# Schematic_Band_Pass.net
KiCad netlist of a schematic drawn in Altium Designer
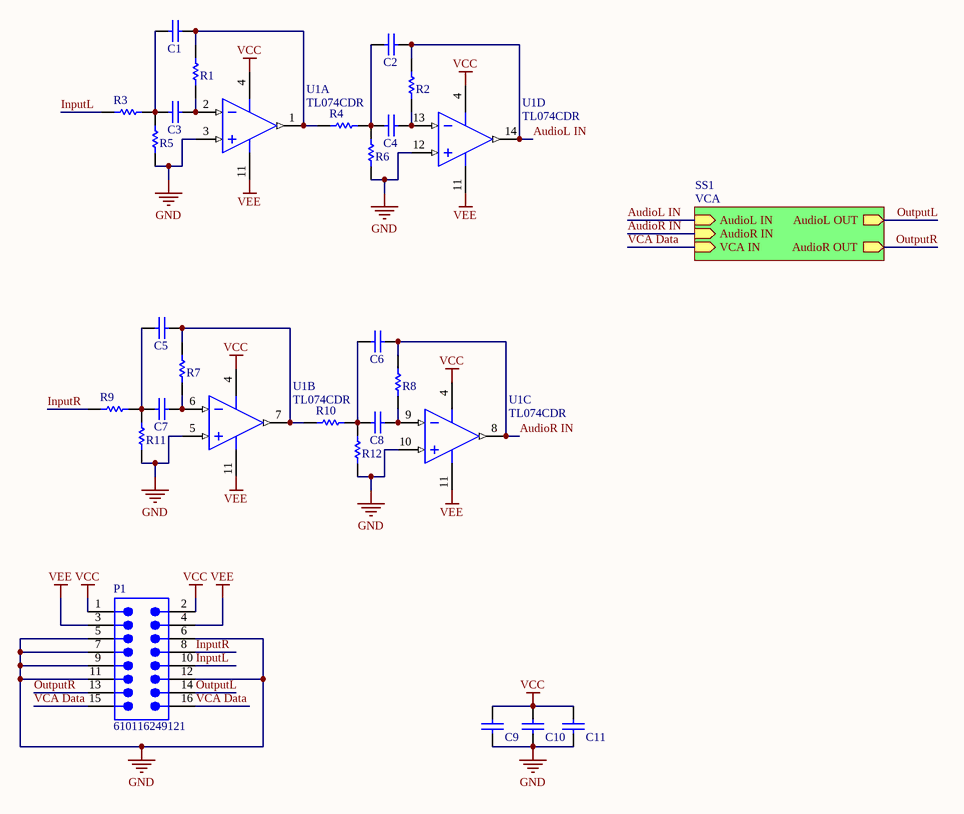
[diagram p0: Schematic Band Pass.SchDoc]

(export (version "E")
  (design (tool "Eeschema 10.0.6"))
  (components
    (comp (ref "C1")
      (value "1206GC102KAT1A")
      (footprint "AVX-1206-2_L")
      (description "Chip Capacitor, 1 nF, +/- 10%, -55 to 125 degC, 1206 (3216 Metric), RoHS, Tape and Reel")
      (fields (field (name "TOLERANCE") "10%") (field (name "MANUFACTURER") "AVX"))
      (libsource (lib "Altium Content Vault") (part "CAP-NP-2"))
    )
    (comp (ref "C2")
      (value "1206GC102KAT1A")
      (footprint "AVX-1206-2_L")
      (description "Chip Capacitor, 1 nF, +/- 10%, -55 to 125 degC, 1206 (3216 Metric), RoHS, Tape and Reel")
      (fields (field (name "TOLERANCE") "10%") (field (name "MANUFACTURER") "AVX"))
      (libsource (lib "Altium Content Vault") (part "CAP-NP-2"))
    )
    (comp (ref "C3")
      (value "1206GC102KAT1A")
      (footprint "AVX-1206-2_L")
      (description "Chip Capacitor, 1 nF, +/- 10%, -55 to 125 degC, 1206 (3216 Metric), RoHS, Tape and Reel")
      (fields (field (name "TOLERANCE") "10%") (field (name "MANUFACTURER") "AVX"))
      (libsource (lib "Altium Content Vault") (part "CAP-NP-2"))
    )
    (comp (ref "C4")
      (value "1206GC102KAT1A")
      (footprint "AVX-1206-2_L")
      (description "Chip Capacitor, 1 nF, +/- 10%, -55 to 125 degC, 1206 (3216 Metric), RoHS, Tape and Reel")
      (fields (field (name "TOLERANCE") "10%") (field (name "MANUFACTURER") "AVX"))
      (libsource (lib "Altium Content Vault") (part "CAP-NP-2"))
    )
    (comp (ref "C5")
      (value "1206GC102KAT1A")
      (footprint "AVX-1206-2_L")
      (description "Chip Capacitor, 1 nF, +/- 10%, -55 to 125 degC, 1206 (3216 Metric), RoHS, Tape and Reel")
      (fields (field (name "TOLERANCE") "10%") (field (name "MANUFACTURER") "AVX"))
      (libsource (lib "Altium Content Vault") (part "CAP-NP-2"))
    )
    (comp (ref "C6")
      (value "1206GC102KAT1A")
      (footprint "AVX-1206-2_L")
      (description "Chip Capacitor, 1 nF, +/- 10%, -55 to 125 degC, 1206 (3216 Metric), RoHS, Tape and Reel")
      (fields (field (name "TOLERANCE") "10%") (field (name "MANUFACTURER") "AVX"))
      (libsource (lib "Altium Content Vault") (part "CAP-NP-2"))
    )
    (comp (ref "C7")
      (value "1206GC102KAT1A")
      (footprint "AVX-1206-2_L")
      (description "Chip Capacitor, 1 nF, +/- 10%, -55 to 125 degC, 1206 (3216 Metric), RoHS, Tape and Reel")
      (fields (field (name "TOLERANCE") "10%") (field (name "MANUFACTURER") "AVX"))
      (libsource (lib "Altium Content Vault") (part "CAP-NP-2"))
    )
    (comp (ref "C8")
      (value "1206GC102KAT1A")
      (footprint "AVX-1206-2_L")
      (description "Chip Capacitor, 1 nF, +/- 10%, -55 to 125 degC, 1206 (3216 Metric), RoHS, Tape and Reel")
      (fields (field (name "TOLERANCE") "10%") (field (name "MANUFACTURER") "AVX"))
      (libsource (lib "Altium Content Vault") (part "CAP-NP-2"))
    )
    (comp (ref "C9")
      (value "1206GC102KAT1A")
      (footprint "AVX-1206-2_L")
      (description "Chip Capacitor, 1 nF, +/- 10%, -55 to 125 degC, 1206 (3216 Metric), RoHS, Tape and Reel")
      (fields (field (name "TOLERANCE") "10%") (field (name "MANUFACTURER") "AVX"))
      (libsource (lib "Altium Content Vault") (part "CAP-NP-2"))
    )
    (comp (ref "C10")
      (value "1206GC102KAT1A")
      (footprint "AVX-1206-2_L")
      (description "Chip Capacitor, 1 nF, +/- 10%, -55 to 125 degC, 1206 (3216 Metric), RoHS, Tape and Reel")
      (fields (field (name "TOLERANCE") "10%") (field (name "MANUFACTURER") "AVX"))
      (libsource (lib "Altium Content Vault") (part "CAP-NP-2"))
    )
    (comp (ref "C11")
      (value "1206GC102KAT1A")
      (footprint "AVX-1206-2_L")
      (description "Chip Capacitor, 1 nF, +/- 10%, -55 to 125 degC, 1206 (3216 Metric), RoHS, Tape and Reel")
      (fields (field (name "TOLERANCE") "10%") (field (name "MANUFACTURER") "AVX"))
      (libsource (lib "Altium Content Vault") (part "CAP-NP-2"))
    )
    (comp (ref "P1")
      (value "610116249121")
      (footprint "610116249121")
      (libsource (lib "Altium Content Vault") (part "Header_Male_2R_16P"))
    )
    (comp (ref "R1")
      (value "ERJ-8GEY0R00V")
      (footprint "RESC3216X70X50NL05T20")
      (fields (field (name "MANUFACTURER") "Panasonic"))
      (libsource (lib "Altium Content Vault") (part "RES"))
    )
    (comp (ref "R2")
      (value "ERJ-8GEY0R00V")
      (footprint "RESC3216X70X50NL05T20")
      (fields (field (name "MANUFACTURER") "Panasonic"))
      (libsource (lib "Altium Content Vault") (part "RES"))
    )
    (comp (ref "R3")
      (value "ERJ-8GEY0R00V")
      (footprint "RESC3216X70X50NL05T20")
      (fields (field (name "MANUFACTURER") "Panasonic"))
      (libsource (lib "Altium Content Vault") (part "RES"))
    )
    (comp (ref "R4")
      (value "ERJ-8GEY0R00V")
      (footprint "RESC3216X70X50NL05T20")
      (fields (field (name "MANUFACTURER") "Panasonic"))
      (libsource (lib "Altium Content Vault") (part "RES"))
    )
    (comp (ref "R5")
      (value "ERJ-8GEY0R00V")
      (footprint "RESC3216X70X50NL05T20")
      (fields (field (name "MANUFACTURER") "Panasonic"))
      (libsource (lib "Altium Content Vault") (part "RES"))
    )
    (comp (ref "R6")
      (value "ERJ-8GEY0R00V")
      (footprint "RESC3216X70X50NL05T20")
      (fields (field (name "MANUFACTURER") "Panasonic"))
      (libsource (lib "Altium Content Vault") (part "RES"))
    )
    (comp (ref "R7")
      (value "ERJ-8GEY0R00V")
      (footprint "RESC3216X70X50NL05T20")
      (fields (field (name "MANUFACTURER") "Panasonic"))
      (libsource (lib "Altium Content Vault") (part "RES"))
    )
    (comp (ref "R8")
      (value "ERJ-8GEY0R00V")
      (footprint "RESC3216X70X50NL05T20")
      (fields (field (name "MANUFACTURER") "Panasonic"))
      (libsource (lib "Altium Content Vault") (part "RES"))
    )
    (comp (ref "R9")
      (value "ERJ-8GEY0R00V")
      (footprint "RESC3216X70X50NL05T20")
      (fields (field (name "MANUFACTURER") "Panasonic"))
      (libsource (lib "Altium Content Vault") (part "RES"))
    )
    (comp (ref "R10")
      (value "ERJ-8GEY0R00V")
      (footprint "RESC3216X70X50NL05T20")
      (fields (field (name "MANUFACTURER") "Panasonic"))
      (libsource (lib "Altium Content Vault") (part "RES"))
    )
    (comp (ref "R11")
      (value "ERJ-8GEY0R00V")
      (footprint "RESC3216X70X50NL05T20")
      (fields (field (name "MANUFACTURER") "Panasonic"))
      (libsource (lib "Altium Content Vault") (part "RES"))
    )
    (comp (ref "R12")
      (value "ERJ-8GEY0R00V")
      (footprint "RESC3216X70X50NL05T20")
      (fields (field (name "MANUFACTURER") "Panasonic"))
      (libsource (lib "Altium Content Vault") (part "RES"))
    )
    (comp (ref "U1")
      (value "TL074CDR")
      (footprint "D0014A_N")
      (fields (field (name "MANUFACTURER") "Texas Instruments"))
      (libsource (lib "Altium Content Vault") (part "TI-TLXX4X_MC3403-X14"))
    )
  )
  (nets
    (net (code "1") (name "/AudioL IN") (class "Default")
      (node (ref "C2") (pin "2") (pinfunction "2_2") (pintype "passive"))
      (node (ref "R2") (pin "2") (pinfunction "2_2") (pintype "passive"))
      (node (ref "U1") (pin "14") (pinfunction "OUT4_14") (pintype "output"))
    )
    (net (code "2") (name "/AudioR IN") (class "Default")
      (node (ref "C6") (pin "2") (pinfunction "2_2") (pintype "passive"))
      (node (ref "R8") (pin "2") (pinfunction "2_2") (pintype "passive"))
      (node (ref "U1") (pin "8") (pinfunction "OUT3_8") (pintype "output"))
    )
    (net (code "3") (name "/InputL") (class "Default")
      (node (ref "P1") (pin "10") (pinfunction "10_10") (pintype "passive"))
      (node (ref "R3") (pin "1") (pinfunction "1_1") (pintype "passive"))
    )
    (net (code "4") (name "/InputR") (class "Default")
      (node (ref "P1") (pin "8") (pinfunction "8_8") (pintype "passive"))
      (node (ref "R9") (pin "1") (pinfunction "1_1") (pintype "passive"))
    )
    (net (code "5") (name "/OutputL") (class "Default")
      (node (ref "P1") (pin "14") (pinfunction "14_14") (pintype "passive"))
    )
    (net (code "6") (name "/OutputR") (class "Default")
      (node (ref "P1") (pin "13") (pinfunction "13_13") (pintype "passive"))
    )
    (net (code "7") (name "/VCA Data") (class "Default")
      (node (ref "P1") (pin "15") (pinfunction "15_15") (pintype "passive"))
      (node (ref "P1") (pin "16") (pinfunction "16_16") (pintype "passive"))
    )
    (net (code "8") (name "GND") (class "Default")
      (node (ref "C10") (pin "1") (pinfunction "1_1") (pintype "passive"))
      (node (ref "C11") (pin "1") (pinfunction "1_1") (pintype "passive"))
      (node (ref "C9") (pin "1") (pinfunction "1_1") (pintype "passive"))
      (node (ref "P1") (pin "11") (pinfunction "11_11") (pintype "passive"))
      (node (ref "P1") (pin "12") (pinfunction "12_12") (pintype "passive"))
      (node (ref "P1") (pin "5") (pinfunction "5_5") (pintype "passive"))
      (node (ref "P1") (pin "6") (pinfunction "6_6") (pintype "passive"))
      (node (ref "P1") (pin "7") (pinfunction "7_7") (pintype "passive"))
      (node (ref "P1") (pin "9") (pinfunction "9_9") (pintype "passive"))
      (node (ref "R11") (pin "1") (pinfunction "1_1") (pintype "passive"))
      (node (ref "R12") (pin "1") (pinfunction "1_1") (pintype "passive"))
      (node (ref "R5") (pin "1") (pinfunction "1_1") (pintype "passive"))
      (node (ref "R6") (pin "1") (pinfunction "1_1") (pintype "passive"))
      (node (ref "U1") (pin "10") (pinfunction "IN3+_10") (pintype "input"))
      (node (ref "U1") (pin "12") (pinfunction "IN4+_12") (pintype "input"))
      (node (ref "U1") (pin "3") (pinfunction "IN1+_3") (pintype "input"))
      (node (ref "U1") (pin "5") (pinfunction "IN2+_5") (pintype "input"))
    )
    (net (code "9") (name "Net-(C1-Pad1)") (class "Default")
      (node (ref "C1") (pin "1") (pinfunction "1_1") (pintype "passive"))
      (node (ref "C3") (pin "1") (pinfunction "1_1") (pintype "passive"))
      (node (ref "R3") (pin "2") (pinfunction "2_2") (pintype "passive"))
      (node (ref "R5") (pin "2") (pinfunction "2_2") (pintype "passive"))
    )
    (net (code "10") (name "Net-(C2-Pad1)") (class "Default")
      (node (ref "C2") (pin "1") (pinfunction "1_1") (pintype "passive"))
      (node (ref "C4") (pin "1") (pinfunction "1_1") (pintype "passive"))
      (node (ref "R4") (pin "2") (pinfunction "2_2") (pintype "passive"))
      (node (ref "R6") (pin "2") (pinfunction "2_2") (pintype "passive"))
    )
    (net (code "11") (name "Net-(C5-Pad1)") (class "Default")
      (node (ref "C5") (pin "1") (pinfunction "1_1") (pintype "passive"))
      (node (ref "C7") (pin "1") (pinfunction "1_1") (pintype "passive"))
      (node (ref "R11") (pin "2") (pinfunction "2_2") (pintype "passive"))
      (node (ref "R9") (pin "2") (pinfunction "2_2") (pintype "passive"))
    )
    (net (code "12") (name "Net-(C6-Pad1)") (class "Default")
      (node (ref "C6") (pin "1") (pinfunction "1_1") (pintype "passive"))
      (node (ref "C8") (pin "1") (pinfunction "1_1") (pintype "passive"))
      (node (ref "R10") (pin "2") (pinfunction "2_2") (pintype "passive"))
      (node (ref "R12") (pin "2") (pinfunction "2_2") (pintype "passive"))
    )
    (net (code "13") (name "Net-(U1A-IN1-)") (class "Default")
      (node (ref "C3") (pin "2") (pinfunction "2_2") (pintype "passive"))
      (node (ref "R1") (pin "1") (pinfunction "1_1") (pintype "passive"))
      (node (ref "U1") (pin "2") (pinfunction "IN1-_2") (pintype "input"))
    )
    (net (code "14") (name "Net-(U1A-OUT1)") (class "Default")
      (node (ref "C1") (pin "2") (pinfunction "2_2") (pintype "passive"))
      (node (ref "R1") (pin "2") (pinfunction "2_2") (pintype "passive"))
      (node (ref "R4") (pin "1") (pinfunction "1_1") (pintype "passive"))
      (node (ref "U1") (pin "1") (pinfunction "OUT1_1") (pintype "output"))
    )
    (net (code "15") (name "Net-(U1B-IN2-)") (class "Default")
      (node (ref "C7") (pin "2") (pinfunction "2_2") (pintype "passive"))
      (node (ref "R7") (pin "1") (pinfunction "1_1") (pintype "passive"))
      (node (ref "U1") (pin "6") (pinfunction "IN2-_6") (pintype "input"))
    )
    (net (code "16") (name "Net-(U1B-OUT2)") (class "Default")
      (node (ref "C5") (pin "2") (pinfunction "2_2") (pintype "passive"))
      (node (ref "R10") (pin "1") (pinfunction "1_1") (pintype "passive"))
      (node (ref "R7") (pin "2") (pinfunction "2_2") (pintype "passive"))
      (node (ref "U1") (pin "7") (pinfunction "OUT2_7") (pintype "output"))
    )
    (net (code "17") (name "Net-(U1C-IN3-)") (class "Default")
      (node (ref "C8") (pin "2") (pinfunction "2_2") (pintype "passive"))
      (node (ref "R8") (pin "1") (pinfunction "1_1") (pintype "passive"))
      (node (ref "U1") (pin "9") (pinfunction "IN3-_9") (pintype "input"))
    )
    (net (code "18") (name "Net-(U1D-IN4-)") (class "Default")
      (node (ref "C4") (pin "2") (pinfunction "2_2") (pintype "passive"))
      (node (ref "R2") (pin "1") (pinfunction "1_1") (pintype "passive"))
      (node (ref "U1") (pin "13") (pinfunction "IN4-_13") (pintype "input"))
    )
    (net (code "19") (name "VCC") (class "Default")
      (node (ref "C10") (pin "2") (pinfunction "2_2") (pintype "passive"))
      (node (ref "C11") (pin "2") (pinfunction "2_2") (pintype "passive"))
      (node (ref "C9") (pin "2") (pinfunction "2_2") (pintype "passive"))
      (node (ref "P1") (pin "1") (pinfunction "1_1") (pintype "passive"))
      (node (ref "P1") (pin "2") (pinfunction "2_2") (pintype "passive"))
      (node (ref "U1") (pin "4") (pinfunction "VCC+_4") (pintype "power_in"))
    )
    (net (code "20") (name "VEE") (class "Default")
      (node (ref "P1") (pin "3") (pinfunction "3_3") (pintype "passive"))
      (node (ref "P1") (pin "4") (pinfunction "4_4") (pintype "passive"))
      (node (ref "U1") (pin "11") (pinfunction "VCC-_11") (pintype "power_in"))
    )
  )
)
